# Optical_Lick_Detector.net
KiCad netlist of a schematic drawn in EAGLE
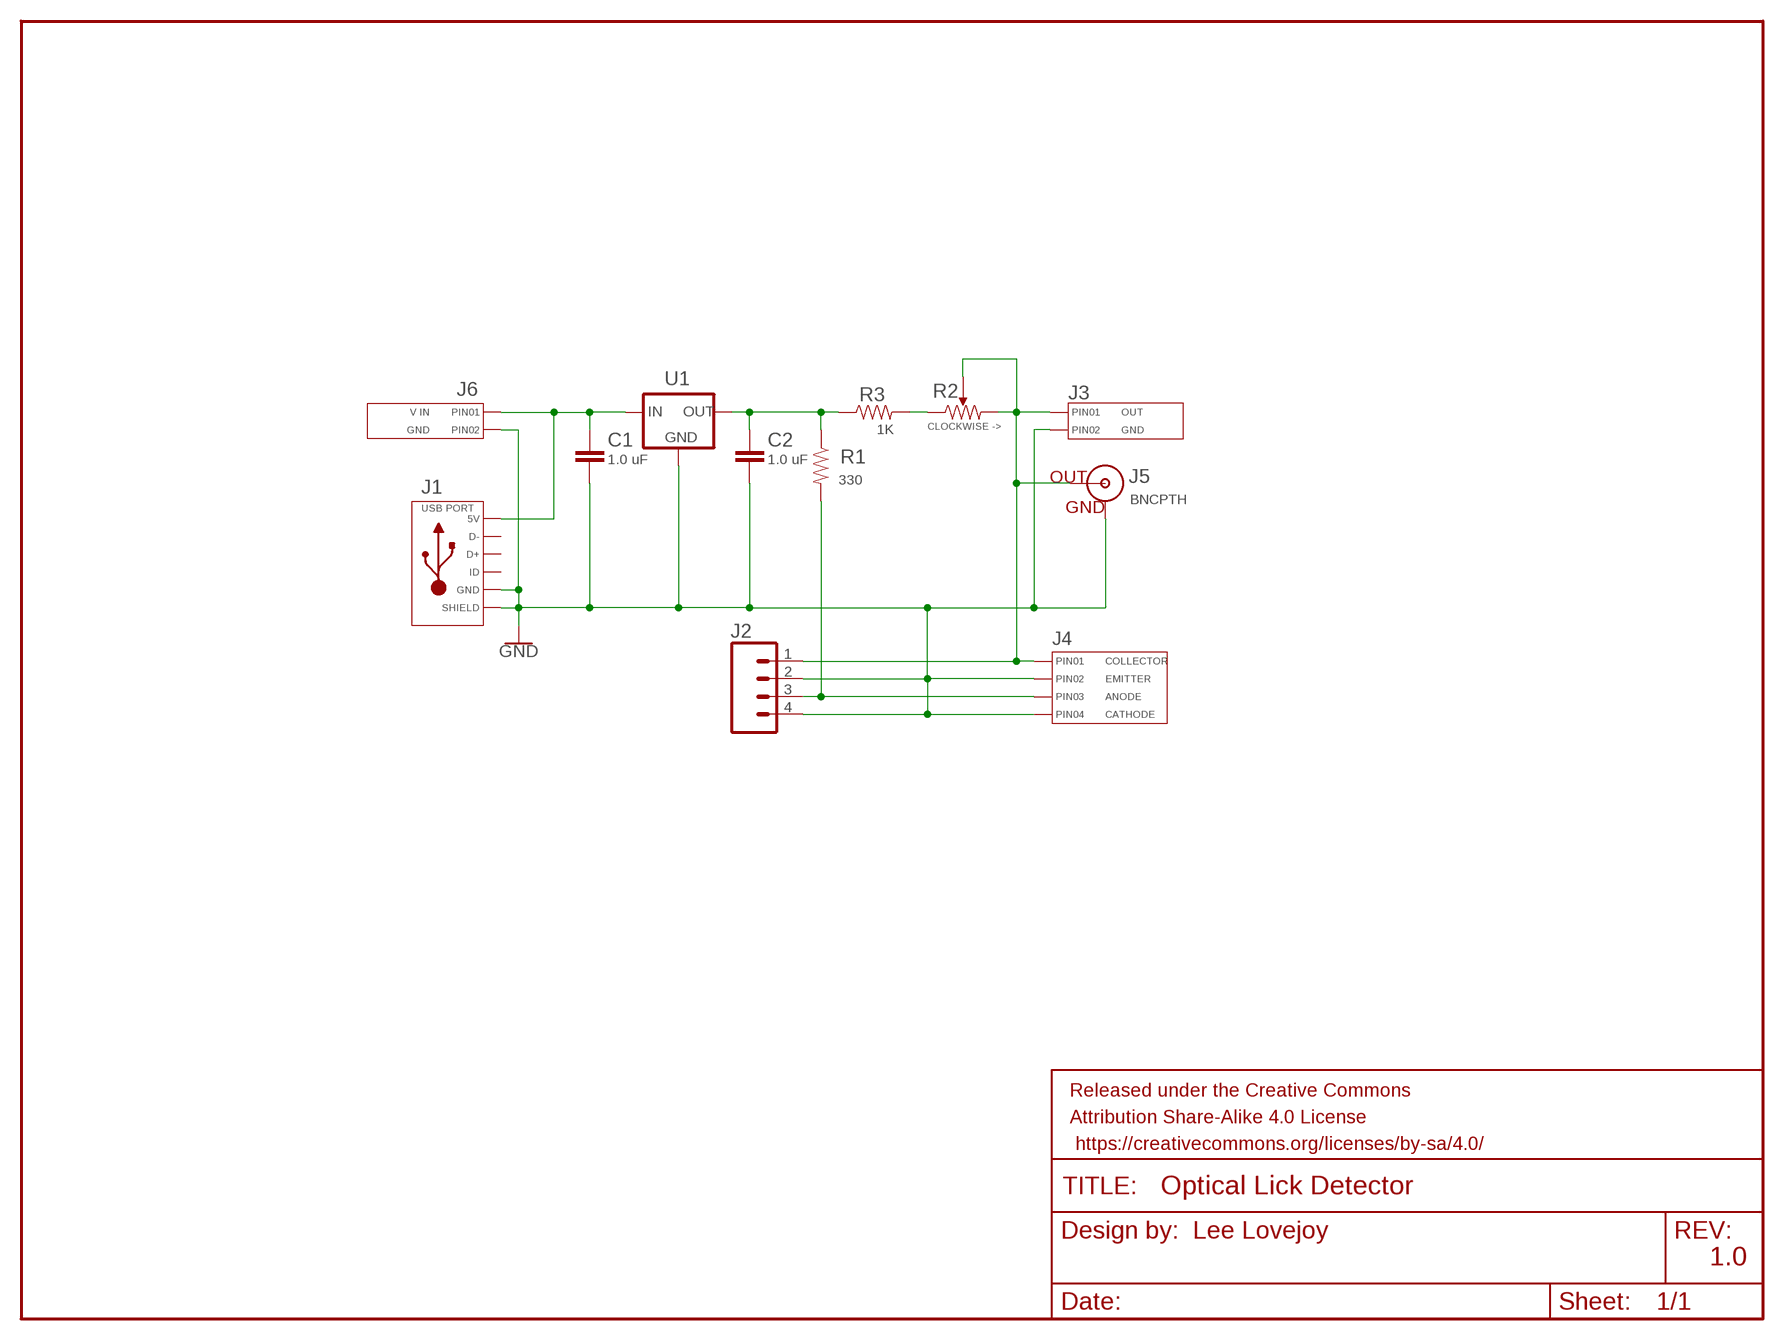
[diagram p0: schematic, sheet 1]

(export (version "E")
  (design (tool "Eeschema 10.0.6"))
  (components
    (comp (ref "C1")
      (value "1.0 uF")
      (footprint "eagle-import:C0603")
      (fields (field (name "MPN") "MF-CAP-0603-1uF "))
      (libsource (lib "eagle-import") (part "CAPACITOR_NP_1.0UF0603"))
    )
    (comp (ref "C2")
      (value "1.0 uF")
      (footprint "eagle-import:C0603")
      (fields (field (name "MPN") "MF-CAP-0603-1uF "))
      (libsource (lib "eagle-import") (part "CAPACITOR_NP_1.0UF0603"))
    )
    (comp (ref "FRAME1")
      (value "FRAME-LETTER")
      (footprint "eagle-import:CREATIVE_COMMONS")
      (libsource (lib "eagle-import") (part "FRAME-LETTER"))
    )
    (comp (ref "J1")
      (value "MF-CON-MICROUSB-RIGHT")
      (footprint "eagle-import:MICROUSB-RIGHT")
      (fields (field (name "HOUSEPART") "YES"))
      (libsource (lib "eagle-import") (part "USB_MICRO_RIGHT"))
    )
    (comp (ref "J2")
      (value "CONN_041X04_NO_SILK")
      (footprint "eagle-import:1X04_NO_SILK")
      (libsource (lib "eagle-import") (part "CONN_041X04_NO_SILK"))
    )
    (comp (ref "J3")
      (value "CONN_023.5MM")
      (footprint "eagle-import:SCREWTERMINAL-3.5MM-2")
      (fields (field (name "MPN") "0393570002") (field (name "LABEL01") "OUT") (field (name "LABEL02") "GND"))
      (libsource (lib "eagle-import") (part "CONN_023.5MM"))
    )
    (comp (ref "J4")
      (value "CONN_04SCREW")
      (footprint "eagle-import:SCREWTERMINAL-3.5MM-4")
      (fields
        (field (name "LABEL01") "COLLECTOR")
        (field (name "LABEL02") "EMITTER")
        (field (name "LABEL03") "ANODE")
        (field (name "LABEL04") "CATHODE")
      )
      (libsource (lib "eagle-import") (part "Training Doors_CONN_04SCREW"))
    )
    (comp (ref "J5")
      (value "BNCPTH")
      (footprint "eagle-import:BNC")
      (libsource (lib "eagle-import") (part "BNCPTH"))
    )
    (comp (ref "J6")
      (value "CONN_023.5MM")
      (footprint "eagle-import:SCREWTERMINAL-3.5MM-2")
      (fields
        (field (name "MPN") "0393570002")
        (field (name "LABEL01") "V IN")
        (field (name "LABEL02") "GND")
      )
      (libsource (lib "eagle-import") (part "CONN_023.5MM"))
    )
    (comp (ref "R1")
      (value "330")
      (footprint "eagle-import:R0402")
      (fields (field (name "HOUSEPART") "yes") (field (name "MPN") "MF-RES-0402-330"))
      (libsource (lib "eagle-import") (part "RESISTOR_330_0402"))
    )
    (comp (ref "R2")
      (value "MF-RES-TC33X-10K")
      (footprint "eagle-import:TC33")
      (fields (field (name "HOUSEPART") "YES") (field (name "TOLERANCE") "25%"))
      (libsource (lib "eagle-import") (part "POTENTIOMETER_TC33_10K"))
    )
    (comp (ref "R3")
      (value "1K")
      (footprint "eagle-import:R0402")
      (fields (field (name "HOUSEPART") "yes") (field (name "MPN") "MF-RES-0402-1K"))
      (libsource (lib "eagle-import") (part "RESISTOR_1K_0402"))
    )
    (comp (ref "U1")
      (value "MIC5200")
      (footprint "eagle-import:SOT223")
      (libsource (lib "eagle-import") (part "MIC5200"))
    )
  )
  (nets
    (net (code "1") (name "GND") (class "Default")
      (node (ref "C1") (pin "P$2") (pinfunction "2_P$2") (pintype "passive"))
      (node (ref "C2") (pin "P$2") (pinfunction "2_P$2") (pintype "passive"))
      (node (ref "J1") (pin "5") (pinfunction "GND_5") (pintype "power_in"))
      (node (ref "J1") (pin "S1") (pinfunction "SLD_S1") (pintype "power_in"))
      (node (ref "J1") (pin "S2") (pinfunction "SLD_S2") (pintype "power_in"))
      (node (ref "J1") (pin "S3") (pinfunction "SLD_S3") (pintype "power_in"))
      (node (ref "J1") (pin "S4") (pinfunction "SLD_S4") (pintype "power_in"))
      (node (ref "J1") (pin "S5") (pinfunction "SLD_S5") (pintype "power_in"))
      (node (ref "J1") (pin "S6") (pinfunction "SLD_S6") (pintype "power_in"))
      (node (ref "J2") (pin "2") (pinfunction "2_2") (pintype "passive"))
      (node (ref "J2") (pin "4") (pinfunction "4_4") (pintype "passive"))
      (node (ref "J3") (pin "2") (pinfunction "PIN2_2") (pintype "bidirectional"))
      (node (ref "J4") (pin "2") (pinfunction "PIN2_2") (pintype "bidirectional"))
      (node (ref "J4") (pin "4") (pinfunction "PIN4_4") (pintype "bidirectional"))
      (node (ref "J5") (pin "GND") (pinfunction "GND_GND") (pintype "bidirectional"))
      (node (ref "J6") (pin "2") (pinfunction "PIN2_2") (pintype "bidirectional"))
      (node (ref "U1") (pin "2") (pinfunction "GND_2") (pintype "input"))
      (node (ref "U1") (pin "4") (pinfunction "GND_4") (pintype "input"))
    )
    (net (code "2") (name "Net-(C1-1)") (class "Default")
      (node (ref "C1") (pin "P$1") (pinfunction "1_P$1") (pintype "passive"))
      (node (ref "J1") (pin "1") (pinfunction "5V_1") (pintype "power_in"))
      (node (ref "J6") (pin "1") (pinfunction "PIN1_1") (pintype "bidirectional"))
      (node (ref "U1") (pin "1") (pinfunction "IN_1") (pintype "input"))
    )
    (net (code "3") (name "Net-(C2-1)") (class "Default")
      (node (ref "C2") (pin "P$1") (pinfunction "1_P$1") (pintype "passive"))
      (node (ref "R1") (pin "P$1") (pinfunction "P$1_P$1") (pintype "passive"))
      (node (ref "R3") (pin "P$1") (pinfunction "P$1_P$1") (pintype "passive"))
      (node (ref "U1") (pin "3") (pinfunction "OUT_3") (pintype "passive"))
    )
    (net (code "4") (name "Net-(J3-PIN1)") (class "Default")
      (node (ref "J2") (pin "1") (pinfunction "1_1") (pintype "passive"))
      (node (ref "J3") (pin "1") (pinfunction "PIN1_1") (pintype "bidirectional"))
      (node (ref "J4") (pin "1") (pinfunction "PIN1_1") (pintype "bidirectional"))
      (node (ref "J5") (pin "S") (pinfunction "OUT_S") (pintype "bidirectional"))
      (node (ref "R2") (pin "P$2") (pinfunction "P$2_P$2") (pintype "passive"))
      (node (ref "R2") (pin "P$3") (pinfunction "P$3_P$3") (pintype "passive"))
    )
    (net (code "5") (name "Net-(J4-PIN3)") (class "Default")
      (node (ref "J2") (pin "3") (pinfunction "3_3") (pintype "passive"))
      (node (ref "J4") (pin "3") (pinfunction "PIN3_3") (pintype "bidirectional"))
      (node (ref "R1") (pin "P$2") (pinfunction "P$2_P$2") (pintype "passive"))
    )
    (net (code "6") (name "Net-(R2-PadP$1)") (class "Default")
      (node (ref "R2") (pin "P$1") (pinfunction "P$1_P$1") (pintype "passive"))
      (node (ref "R3") (pin "P$2") (pinfunction "P$2_P$2") (pintype "passive"))
    )
    (net (code "7") (name "unconnected-(J1-D+-Pad3)") (class "Default")
      (node (ref "J1") (pin "3") (pinfunction "D+_3") (pintype "bidirectional"))
    )
    (net (code "8") (name "unconnected-(J1-D--Pad2)") (class "Default")
      (node (ref "J1") (pin "2") (pinfunction "D-_2") (pintype "bidirectional"))
    )
    (net (code "9") (name "unconnected-(J1-ID-Pad4)") (class "Default")
      (node (ref "J1") (pin "4") (pinfunction "ID_4") (pintype "bidirectional"))
    )
  )
)
